# quadrature.net
KiCad netlist of a schematic drawn in EAGLE
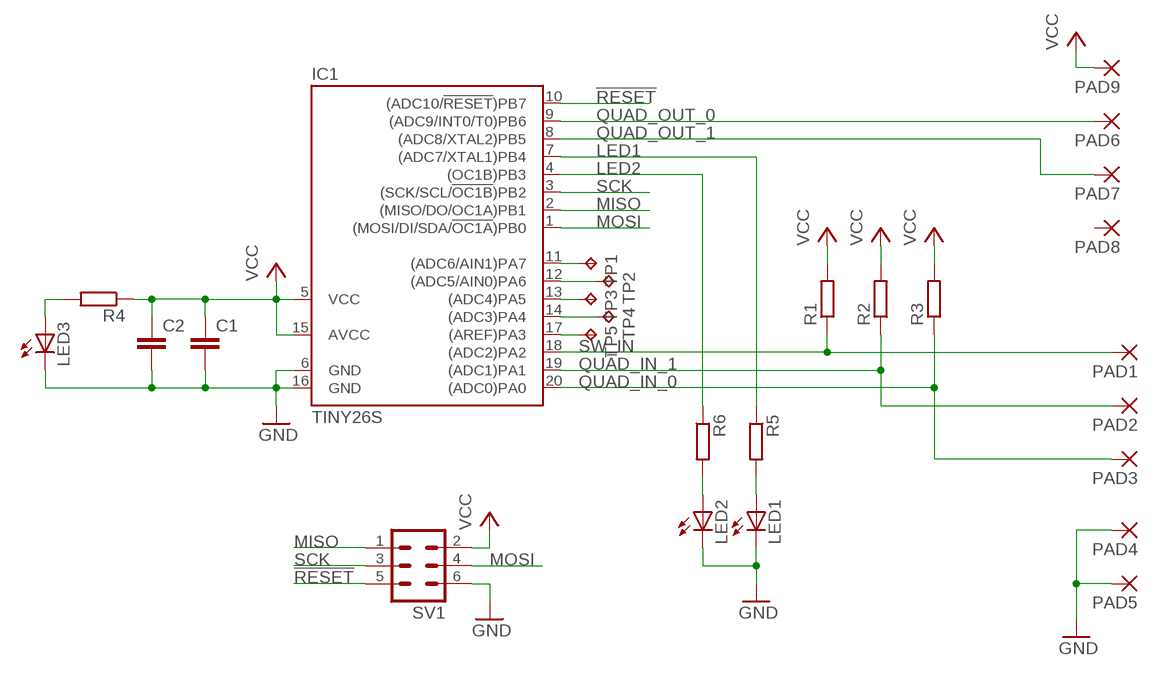
[diagram p0: schematic, sheet 1]

(export (version "E")
  (design (tool "Eeschema 10.0.6"))
  (components
    (comp (ref "C1")
      (value "C-EUC0603")
      (footprint "eagle-import:C0603")
      (libsource (lib "eagle-import") (part "C-EUC0603"))
    )
    (comp (ref "C2")
      (value "C-EUC0603")
      (footprint "eagle-import:C0603")
      (libsource (lib "eagle-import") (part "C-EUC0603"))
    )
    (comp (ref "IC1")
      (value "TINY26S")
      (footprint "eagle-import:SO20L")
      (fields (field (name "MPN") "ATTINY261-20SU"))
      (libsource (lib "eagle-import") (part "TINY26S"))
    )
    (comp (ref "LED1")
      (value "LEDCHIP-LED0603")
      (footprint "eagle-import:CHIP-LED0603")
      (libsource (lib "eagle-import") (part "LEDCHIP-LED0603"))
    )
    (comp (ref "LED2")
      (value "LEDCHIP-LED0603")
      (footprint "eagle-import:CHIP-LED0603")
      (libsource (lib "eagle-import") (part "LEDCHIP-LED0603"))
    )
    (comp (ref "LED3")
      (value "LEDCHIP-LED0603")
      (footprint "eagle-import:CHIP-LED0603")
      (libsource (lib "eagle-import") (part "LEDCHIP-LED0603"))
    )
    (comp (ref "PAD1")
      (value "1,6/0,8")
      (footprint "eagle-import:1,6_0,8")
      (libsource (lib "eagle-import") (part "1,6/0,8"))
    )
    (comp (ref "PAD2")
      (value "1,6/0,8")
      (footprint "eagle-import:1,6_0,8")
      (libsource (lib "eagle-import") (part "1,6/0,8"))
    )
    (comp (ref "PAD3")
      (value "1,6/0,8")
      (footprint "eagle-import:1,6_0,8")
      (libsource (lib "eagle-import") (part "1,6/0,8"))
    )
    (comp (ref "PAD4")
      (value "1,6/0,8")
      (footprint "eagle-import:1,6_0,8")
      (libsource (lib "eagle-import") (part "1,6/0,8"))
    )
    (comp (ref "PAD5")
      (value "1,6/0,8")
      (footprint "eagle-import:1,6_0,8")
      (libsource (lib "eagle-import") (part "1,6/0,8"))
    )
    (comp (ref "PAD6")
      (value "1,6/0,8")
      (footprint "eagle-import:1,6_0,8")
      (libsource (lib "eagle-import") (part "1,6/0,8"))
    )
    (comp (ref "PAD7")
      (value "1,6/0,8")
      (footprint "eagle-import:1,6_0,8")
      (libsource (lib "eagle-import") (part "1,6/0,8"))
    )
    (comp (ref "PAD8")
      (value "1,6/0,8")
      (footprint "eagle-import:1,6_0,8")
      (libsource (lib "eagle-import") (part "1,6/0,8"))
    )
    (comp (ref "PAD9")
      (value "1,6/0,8")
      (footprint "eagle-import:1,6_0,8")
      (libsource (lib "eagle-import") (part "1,6/0,8"))
    )
    (comp (ref "R1")
      (value "R-EU_R0603")
      (footprint "eagle-import:R0603")
      (libsource (lib "eagle-import") (part "R-EU_R0603"))
    )
    (comp (ref "R2")
      (value "R-EU_R0603")
      (footprint "eagle-import:R0603")
      (libsource (lib "eagle-import") (part "R-EU_R0603"))
    )
    (comp (ref "R3")
      (value "R-EU_R0603")
      (footprint "eagle-import:R0603")
      (libsource (lib "eagle-import") (part "R-EU_R0603"))
    )
    (comp (ref "R4")
      (value "R-EU_R0603")
      (footprint "eagle-import:R0603")
      (libsource (lib "eagle-import") (part "R-EU_R0603"))
    )
    (comp (ref "R5")
      (value "R-EU_R0603")
      (footprint "eagle-import:R0603")
      (libsource (lib "eagle-import") (part "R-EU_R0603"))
    )
    (comp (ref "R6")
      (value "R-EU_R0603")
      (footprint "eagle-import:R0603")
      (libsource (lib "eagle-import") (part "R-EU_R0603"))
    )
    (comp (ref "SV1")
      (value "ML6")
      (footprint "eagle-import:ML6")
      (libsource (lib "eagle-import") (part "ML6"))
    )
    (comp (ref "TP1")
      (value "TPB1,27")
      (footprint "eagle-import:B1,27")
      (libsource (lib "eagle-import") (part "TPB1,27"))
    )
    (comp (ref "TP2")
      (value "TPB1,27")
      (footprint "eagle-import:B1,27")
      (libsource (lib "eagle-import") (part "TPB1,27"))
    )
    (comp (ref "TP3")
      (value "TPB1,27")
      (footprint "eagle-import:B1,27")
      (libsource (lib "eagle-import") (part "TPB1,27"))
    )
    (comp (ref "TP4")
      (value "TPB1,27")
      (footprint "eagle-import:B1,27")
      (libsource (lib "eagle-import") (part "TPB1,27"))
    )
    (comp (ref "TP5")
      (value "TPB1,27")
      (footprint "eagle-import:B1,27")
      (libsource (lib "eagle-import") (part "TPB1,27"))
    )
  )
  (nets
    (net (code "1") (name "/LED1") (class "Default")
      (node (ref "IC1") (pin "7") (pinfunction "(ADC7/XTAL1)PB4_7") (pintype "bidirectional"))
      (node (ref "R5") (pin "1") (pinfunction "1_1") (pintype "passive"))
    )
    (net (code "2") (name "/LED2") (class "Default")
      (node (ref "IC1") (pin "4") (pinfunction "(OC1B)PB3_4") (pintype "bidirectional"))
      (node (ref "R6") (pin "1") (pinfunction "1_1") (pintype "passive"))
    )
    (net (code "3") (name "/MISO") (class "Default")
      (node (ref "IC1") (pin "2") (pinfunction "(MISO/DO/OC1A)PB1_2") (pintype "bidirectional"))
      (node (ref "SV1") (pin "1") (pinfunction "1_1") (pintype "passive"))
    )
    (net (code "4") (name "/MOSI") (class "Default")
      (node (ref "IC1") (pin "1") (pinfunction "(MOSI/DI/SDA/~{OC1A})PB0_1") (pintype "bidirectional"))
      (node (ref "SV1") (pin "4") (pinfunction "4_4") (pintype "passive"))
    )
    (net (code "5") (name "/QUAD_IN_0") (class "Default")
      (node (ref "IC1") (pin "20") (pinfunction "(ADC0)PA0_20") (pintype "bidirectional"))
      (node (ref "PAD3") (pin "1") (pinfunction "P_1") (pintype "passive"))
      (node (ref "R3") (pin "1") (pinfunction "1_1") (pintype "passive"))
    )
    (net (code "6") (name "/QUAD_IN_1") (class "Default")
      (node (ref "IC1") (pin "19") (pinfunction "(ADC1)PA1_19") (pintype "bidirectional"))
      (node (ref "PAD2") (pin "1") (pinfunction "P_1") (pintype "passive"))
      (node (ref "R2") (pin "1") (pinfunction "1_1") (pintype "passive"))
    )
    (net (code "7") (name "/QUAD_OUT_0") (class "Default")
      (node (ref "IC1") (pin "9") (pinfunction "(ADC9/INT0/T0)PB6_9") (pintype "bidirectional"))
      (node (ref "PAD6") (pin "1") (pinfunction "P_1") (pintype "passive"))
    )
    (net (code "8") (name "/QUAD_OUT_1") (class "Default")
      (node (ref "IC1") (pin "8") (pinfunction "(ADC8/XTAL2)PB5_8") (pintype "bidirectional"))
      (node (ref "PAD7") (pin "1") (pinfunction "P_1") (pintype "passive"))
    )
    (net (code "9") (name "/SCK") (class "Default")
      (node (ref "IC1") (pin "3") (pinfunction "(SCK/SCL/~{OC1B})PB2_3") (pintype "bidirectional"))
      (node (ref "SV1") (pin "3") (pinfunction "3_3") (pintype "passive"))
    )
    (net (code "10") (name "/SW_IN") (class "Default")
      (node (ref "IC1") (pin "18") (pinfunction "(ADC2)PA2_18") (pintype "bidirectional"))
      (node (ref "PAD1") (pin "1") (pinfunction "P_1") (pintype "passive"))
      (node (ref "R1") (pin "1") (pinfunction "1_1") (pintype "passive"))
    )
    (net (code "11") (name "/~{RESET}") (class "Default")
      (node (ref "IC1") (pin "10") (pinfunction "(ADC10/~{RESET})PB7_10") (pintype "bidirectional"))
      (node (ref "SV1") (pin "5") (pinfunction "5_5") (pintype "passive"))
    )
    (net (code "12") (name "GND") (class "Default")
      (node (ref "C1") (pin "2") (pinfunction "2_2") (pintype "passive"))
      (node (ref "C2") (pin "2") (pinfunction "2_2") (pintype "passive"))
      (node (ref "IC1") (pin "16") (pinfunction "GND_16") (pintype "power_in"))
      (node (ref "IC1") (pin "6") (pinfunction "GND_6") (pintype "power_in"))
      (node (ref "LED1") (pin "C") (pinfunction "C_C") (pintype "passive"))
      (node (ref "LED2") (pin "C") (pinfunction "C_C") (pintype "passive"))
      (node (ref "LED3") (pin "C") (pinfunction "C_C") (pintype "passive"))
      (node (ref "PAD4") (pin "1") (pinfunction "P_1") (pintype "passive"))
      (node (ref "PAD5") (pin "1") (pinfunction "P_1") (pintype "passive"))
      (node (ref "SV1") (pin "6") (pinfunction "6_6") (pintype "passive"))
    )
    (net (code "13") (name "Net-(IC1-(ADC3)PA4)") (class "Default")
      (node (ref "IC1") (pin "14") (pinfunction "(ADC3)PA4_14") (pintype "bidirectional"))
      (node (ref "TP4") (pin "TP") (pinfunction "TP_TP") (pintype "input"))
    )
    (net (code "14") (name "Net-(IC1-(ADC4)PA5)") (class "Default")
      (node (ref "IC1") (pin "13") (pinfunction "(ADC4)PA5_13") (pintype "bidirectional"))
      (node (ref "TP3") (pin "TP") (pinfunction "TP_TP") (pintype "input"))
    )
    (net (code "15") (name "Net-(IC1-(ADC5{slash}AIN0)PA6)") (class "Default")
      (node (ref "IC1") (pin "12") (pinfunction "(ADC5/AIN0)PA6_12") (pintype "bidirectional"))
      (node (ref "TP2") (pin "TP") (pinfunction "TP_TP") (pintype "input"))
    )
    (net (code "16") (name "Net-(IC1-(ADC6{slash}AIN1)PA7)") (class "Default")
      (node (ref "IC1") (pin "11") (pinfunction "(ADC6/AIN1)PA7_11") (pintype "bidirectional"))
      (node (ref "TP1") (pin "TP") (pinfunction "TP_TP") (pintype "input"))
    )
    (net (code "17") (name "Net-(IC1-(AREF)PA3)") (class "Default")
      (node (ref "IC1") (pin "17") (pinfunction "(AREF)PA3_17") (pintype "bidirectional"))
      (node (ref "TP5") (pin "TP") (pinfunction "TP_TP") (pintype "input"))
    )
    (net (code "18") (name "Net-(LED1-PadA)") (class "Default")
      (node (ref "LED1") (pin "A") (pinfunction "A_A") (pintype "passive"))
      (node (ref "R5") (pin "2") (pinfunction "2_2") (pintype "passive"))
    )
    (net (code "19") (name "Net-(LED2-PadA)") (class "Default")
      (node (ref "LED2") (pin "A") (pinfunction "A_A") (pintype "passive"))
      (node (ref "R6") (pin "2") (pinfunction "2_2") (pintype "passive"))
    )
    (net (code "20") (name "Net-(LED3-PadA)") (class "Default")
      (node (ref "LED3") (pin "A") (pinfunction "A_A") (pintype "passive"))
      (node (ref "R4") (pin "2") (pinfunction "2_2") (pintype "passive"))
    )
    (net (code "21") (name "VCC") (class "Default")
      (node (ref "C1") (pin "1") (pinfunction "1_1") (pintype "passive"))
      (node (ref "C2") (pin "1") (pinfunction "1_1") (pintype "passive"))
      (node (ref "IC1") (pin "15") (pinfunction "AVCC_15") (pintype "power_in"))
      (node (ref "IC1") (pin "5") (pinfunction "VCC_5") (pintype "power_in"))
      (node (ref "PAD9") (pin "1") (pinfunction "P_1") (pintype "passive"))
      (node (ref "R1") (pin "2") (pinfunction "2_2") (pintype "passive"))
      (node (ref "R2") (pin "2") (pinfunction "2_2") (pintype "passive"))
      (node (ref "R3") (pin "2") (pinfunction "2_2") (pintype "passive"))
      (node (ref "R4") (pin "1") (pinfunction "1_1") (pintype "passive"))
      (node (ref "SV1") (pin "2") (pinfunction "2_2") (pintype "passive"))
    )
    (net (code "22") (name "unconnected-(PAD8-P-Pad1)") (class "Default")
      (node (ref "PAD8") (pin "1") (pinfunction "P_1") (pintype "passive"))
    )
  )
)
